# FX-Flash_DIP_rev_C.net
KiCad netlist of a schematic drawn in EAGLE
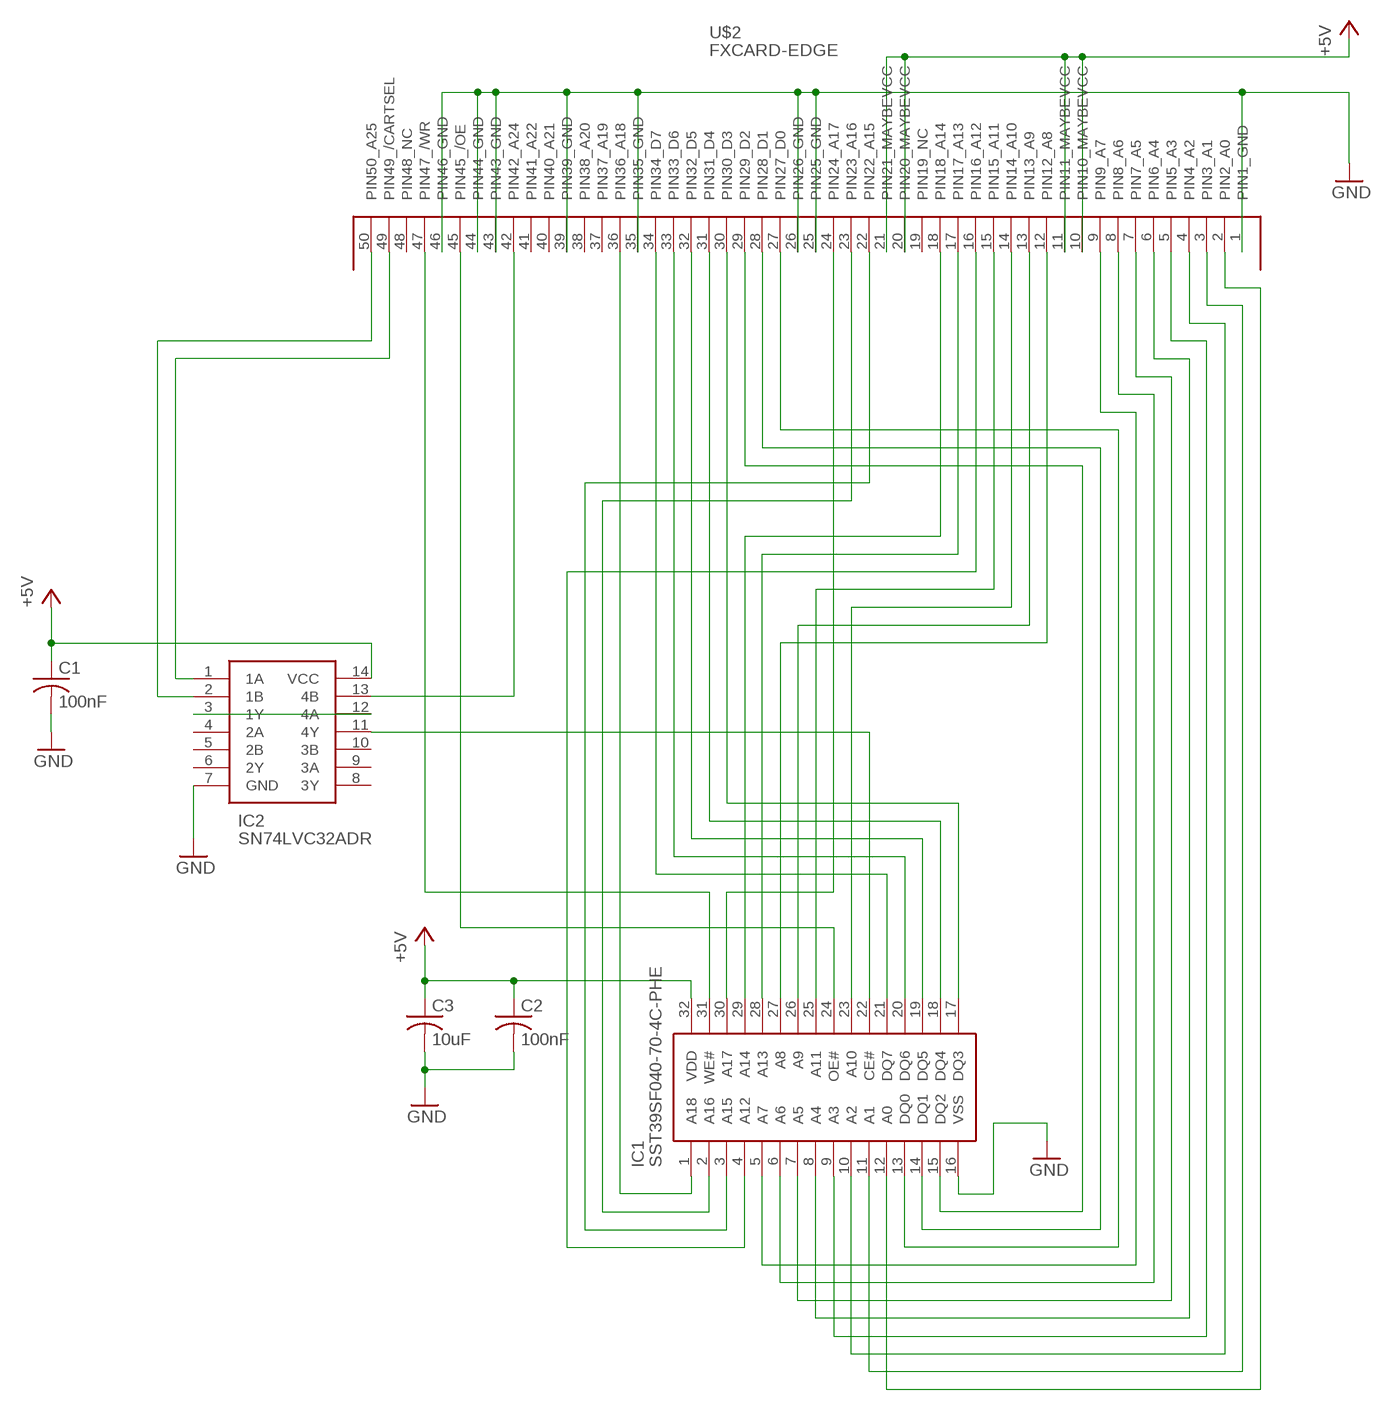
[diagram p0: schematic, sheet 1]

(export (version "E")
  (design (tool "Eeschema 10.0.6"))
  (components
    (comp (ref "C1")
      (value "100nF")
      (footprint "eagle-import:C0805")
      (libsource (lib "eagle-import") (part "C-USC0805"))
    )
    (comp (ref "C2")
      (value "100nF")
      (footprint "eagle-import:C0805")
      (libsource (lib "eagle-import") (part "C-USC0805"))
    )
    (comp (ref "C3")
      (value "10uF")
      (footprint "eagle-import:C0805")
      (libsource (lib "eagle-import") (part "C-USC0805"))
    )
    (comp (ref "IC1")
      (value "SST39SF040-70-4C-PHE")
      (footprint "eagle-import:DIP1556W56P254L4191H508Q32N")
      (fields
        (field (name "MOUSER_PART_NUMBER") "804-39SF0407CPHE")
        (field (name "RS_PART_NUMBER") "8104037P")
      )
      (libsource (lib "eagle-import") (part "SST39SF040-70-4C-PHE"))
    )
    (comp (ref "IC2")
      (value "SN74LVC32ADR")
      (footprint "eagle-import:SOIC127P600X175-14N")
      (fields (field (name "MOUSER_PART_NUMBER") "595-SN74LVC32ADR"))
      (libsource (lib "eagle-import") (part "SN74LVC32ADR"))
    )
    (comp (ref "U$2")
      (value "FXCARD-EDGE")
      (footprint "eagle-import:FXCARD-EDGE")
      (libsource (lib "eagle-import") (part "FXCARD-EDGE"))
    )
  )
  (nets
    (net (code "1") (name "+5V") (class "Default")
      (node (ref "C1") (pin "1") (pinfunction "1_1") (pintype "passive"))
      (node (ref "C2") (pin "1") (pinfunction "1_1") (pintype "passive"))
      (node (ref "C3") (pin "1") (pinfunction "1_1") (pintype "passive"))
      (node (ref "IC1") (pin "32") (pinfunction "VDD_32") (pintype "bidirectional"))
      (node (ref "IC2") (pin "14") (pinfunction "VCC_14") (pintype "bidirectional"))
      (node (ref "U$2") (pin "10") (pinfunction "PIN10_MAYBEVCC_10") (pintype "bidirectional"))
      (node (ref "U$2") (pin "11") (pinfunction "PIN11_MAYBEVCC_11") (pintype "bidirectional"))
      (node (ref "U$2") (pin "20") (pinfunction "PIN20_MAYBEVCC_20") (pintype "bidirectional"))
      (node (ref "U$2") (pin "21") (pinfunction "PIN21_MAYBEVCC_21") (pintype "bidirectional"))
    )
    (net (code "2") (name "GND") (class "Default")
      (node (ref "C1") (pin "2") (pinfunction "2_2") (pintype "passive"))
      (node (ref "C2") (pin "2") (pinfunction "2_2") (pintype "passive"))
      (node (ref "C3") (pin "2") (pinfunction "2_2") (pintype "passive"))
      (node (ref "IC1") (pin "16") (pinfunction "VSS_16") (pintype "bidirectional"))
      (node (ref "IC2") (pin "7") (pinfunction "GND_7") (pintype "bidirectional"))
      (node (ref "U$2") (pin "1") (pinfunction "PIN1_GND_1") (pintype "power_in"))
      (node (ref "U$2") (pin "25") (pinfunction "PIN25_GND_25") (pintype "power_in"))
      (node (ref "U$2") (pin "26") (pinfunction "PIN26_GND_26") (pintype "power_in"))
      (node (ref "U$2") (pin "35") (pinfunction "PIN35_GND_35") (pintype "power_in"))
      (node (ref "U$2") (pin "39") (pinfunction "PIN39_GND_39") (pintype "power_in"))
      (node (ref "U$2") (pin "43") (pinfunction "PIN43_GND_43") (pintype "power_in"))
      (node (ref "U$2") (pin "44") (pinfunction "PIN44_GND_44") (pintype "power_in"))
      (node (ref "U$2") (pin "46") (pinfunction "PIN46_GND_46") (pintype "power_in"))
    )
    (net (code "3") (name "Net-(IC1-A0)") (class "Default")
      (node (ref "IC1") (pin "12") (pinfunction "A0_12") (pintype "bidirectional"))
      (node (ref "U$2") (pin "2") (pinfunction "PIN2_A0_2") (pintype "bidirectional"))
    )
    (net (code "4") (name "Net-(IC1-A1)") (class "Default")
      (node (ref "IC1") (pin "11") (pinfunction "A1_11") (pintype "bidirectional"))
      (node (ref "U$2") (pin "3") (pinfunction "PIN3_A1_3") (pintype "bidirectional"))
    )
    (net (code "5") (name "Net-(IC1-A2)") (class "Default")
      (node (ref "IC1") (pin "10") (pinfunction "A2_10") (pintype "bidirectional"))
      (node (ref "U$2") (pin "4") (pinfunction "PIN4_A2_4") (pintype "bidirectional"))
    )
    (net (code "6") (name "Net-(IC1-A3)") (class "Default")
      (node (ref "IC1") (pin "9") (pinfunction "A3_9") (pintype "bidirectional"))
      (node (ref "U$2") (pin "5") (pinfunction "PIN5_A3_5") (pintype "bidirectional"))
    )
    (net (code "7") (name "Net-(IC1-A4)") (class "Default")
      (node (ref "IC1") (pin "8") (pinfunction "A4_8") (pintype "bidirectional"))
      (node (ref "U$2") (pin "6") (pinfunction "PIN6_A4_6") (pintype "bidirectional"))
    )
    (net (code "8") (name "Net-(IC1-A5)") (class "Default")
      (node (ref "IC1") (pin "7") (pinfunction "A5_7") (pintype "bidirectional"))
      (node (ref "U$2") (pin "7") (pinfunction "PIN7_A5_7") (pintype "bidirectional"))
    )
    (net (code "9") (name "Net-(IC1-A6)") (class "Default")
      (node (ref "IC1") (pin "6") (pinfunction "A6_6") (pintype "bidirectional"))
      (node (ref "U$2") (pin "8") (pinfunction "PIN8_A6_8") (pintype "bidirectional"))
    )
    (net (code "10") (name "Net-(IC1-A7)") (class "Default")
      (node (ref "IC1") (pin "5") (pinfunction "A7_5") (pintype "bidirectional"))
      (node (ref "U$2") (pin "9") (pinfunction "PIN9_A7_9") (pintype "bidirectional"))
    )
    (net (code "11") (name "Net-(IC1-A8)") (class "Default")
      (node (ref "IC1") (pin "27") (pinfunction "A8_27") (pintype "bidirectional"))
      (node (ref "U$2") (pin "12") (pinfunction "PIN12_A8_12") (pintype "bidirectional"))
    )
    (net (code "12") (name "Net-(IC1-A9)") (class "Default")
      (node (ref "IC1") (pin "26") (pinfunction "A9_26") (pintype "bidirectional"))
      (node (ref "U$2") (pin "13") (pinfunction "PIN13_A9_13") (pintype "bidirectional"))
    )
    (net (code "13") (name "Net-(IC1-A10)") (class "Default")
      (node (ref "IC1") (pin "23") (pinfunction "A10_23") (pintype "bidirectional"))
      (node (ref "U$2") (pin "14") (pinfunction "PIN14_A10_14") (pintype "bidirectional"))
    )
    (net (code "14") (name "Net-(IC1-A11)") (class "Default")
      (node (ref "IC1") (pin "25") (pinfunction "A11_25") (pintype "bidirectional"))
      (node (ref "U$2") (pin "15") (pinfunction "PIN15_A11_15") (pintype "bidirectional"))
    )
    (net (code "15") (name "Net-(IC1-A12)") (class "Default")
      (node (ref "IC1") (pin "4") (pinfunction "A12_4") (pintype "bidirectional"))
      (node (ref "U$2") (pin "16") (pinfunction "PIN16_A12_16") (pintype "bidirectional"))
    )
    (net (code "16") (name "Net-(IC1-A13)") (class "Default")
      (node (ref "IC1") (pin "28") (pinfunction "A13_28") (pintype "bidirectional"))
      (node (ref "U$2") (pin "17") (pinfunction "PIN17_A13_17") (pintype "bidirectional"))
    )
    (net (code "17") (name "Net-(IC1-A14)") (class "Default")
      (node (ref "IC1") (pin "29") (pinfunction "A14_29") (pintype "bidirectional"))
      (node (ref "U$2") (pin "18") (pinfunction "PIN18_A14_18") (pintype "bidirectional"))
    )
    (net (code "18") (name "Net-(IC1-A15)") (class "Default")
      (node (ref "IC1") (pin "3") (pinfunction "A15_3") (pintype "bidirectional"))
      (node (ref "U$2") (pin "22") (pinfunction "PIN22_A15_22") (pintype "bidirectional"))
    )
    (net (code "19") (name "Net-(IC1-A16)") (class "Default")
      (node (ref "IC1") (pin "2") (pinfunction "A16_2") (pintype "bidirectional"))
      (node (ref "U$2") (pin "23") (pinfunction "PIN23_A16_23") (pintype "bidirectional"))
    )
    (net (code "20") (name "Net-(IC1-A17)") (class "Default")
      (node (ref "IC1") (pin "30") (pinfunction "A17_30") (pintype "bidirectional"))
      (node (ref "U$2") (pin "24") (pinfunction "PIN24_A17_24") (pintype "bidirectional"))
    )
    (net (code "21") (name "Net-(IC1-A18)") (class "Default")
      (node (ref "IC1") (pin "1") (pinfunction "A18_1") (pintype "bidirectional"))
      (node (ref "U$2") (pin "36") (pinfunction "PIN36_A18_36") (pintype "bidirectional"))
    )
    (net (code "22") (name "Net-(IC1-CE#)") (class "Default")
      (node (ref "IC1") (pin "22") (pinfunction "CE#_22") (pintype "bidirectional"))
      (node (ref "IC2") (pin "11") (pinfunction "4Y_11") (pintype "bidirectional"))
    )
    (net (code "23") (name "Net-(IC1-DQ0)") (class "Default")
      (node (ref "IC1") (pin "13") (pinfunction "DQ0_13") (pintype "bidirectional"))
      (node (ref "U$2") (pin "27") (pinfunction "PIN27_D0_27") (pintype "bidirectional"))
    )
    (net (code "24") (name "Net-(IC1-DQ1)") (class "Default")
      (node (ref "IC1") (pin "14") (pinfunction "DQ1_14") (pintype "bidirectional"))
      (node (ref "U$2") (pin "28") (pinfunction "PIN28_D1_28") (pintype "bidirectional"))
    )
    (net (code "25") (name "Net-(IC1-DQ2)") (class "Default")
      (node (ref "IC1") (pin "15") (pinfunction "DQ2_15") (pintype "bidirectional"))
      (node (ref "U$2") (pin "29") (pinfunction "PIN29_D2_29") (pintype "bidirectional"))
    )
    (net (code "26") (name "Net-(IC1-DQ3)") (class "Default")
      (node (ref "IC1") (pin "17") (pinfunction "DQ3_17") (pintype "bidirectional"))
      (node (ref "U$2") (pin "30") (pinfunction "PIN30_D3_30") (pintype "bidirectional"))
    )
    (net (code "27") (name "Net-(IC1-DQ4)") (class "Default")
      (node (ref "IC1") (pin "18") (pinfunction "DQ4_18") (pintype "bidirectional"))
      (node (ref "U$2") (pin "31") (pinfunction "PIN31_D4_31") (pintype "bidirectional"))
    )
    (net (code "28") (name "Net-(IC1-DQ5)") (class "Default")
      (node (ref "IC1") (pin "19") (pinfunction "DQ5_19") (pintype "bidirectional"))
      (node (ref "U$2") (pin "32") (pinfunction "PIN32_D5_32") (pintype "bidirectional"))
    )
    (net (code "29") (name "Net-(IC1-DQ6)") (class "Default")
      (node (ref "IC1") (pin "20") (pinfunction "DQ6_20") (pintype "bidirectional"))
      (node (ref "U$2") (pin "33") (pinfunction "PIN33_D6_33") (pintype "bidirectional"))
    )
    (net (code "30") (name "Net-(IC1-DQ7)") (class "Default")
      (node (ref "IC1") (pin "21") (pinfunction "DQ7_21") (pintype "bidirectional"))
      (node (ref "U$2") (pin "34") (pinfunction "PIN34_D7_34") (pintype "bidirectional"))
    )
    (net (code "31") (name "Net-(IC1-OE#)") (class "Default")
      (node (ref "IC1") (pin "24") (pinfunction "OE#_24") (pintype "bidirectional"))
      (node (ref "U$2") (pin "45") (pinfunction "PIN45_/OE_45") (pintype "bidirectional"))
    )
    (net (code "32") (name "Net-(IC1-WE#)") (class "Default")
      (node (ref "IC1") (pin "31") (pinfunction "WE#_31") (pintype "bidirectional"))
      (node (ref "U$2") (pin "47") (pinfunction "PIN47_/WR_47") (pintype "bidirectional"))
    )
    (net (code "33") (name "Net-(IC2-1A)") (class "Default")
      (node (ref "IC2") (pin "1") (pinfunction "1A_1") (pintype "bidirectional"))
      (node (ref "U$2") (pin "49") (pinfunction "PIN49_/CARTSEL_49") (pintype "bidirectional"))
    )
    (net (code "34") (name "Net-(IC2-1B)") (class "Default")
      (node (ref "IC2") (pin "2") (pinfunction "1B_2") (pintype "bidirectional"))
      (node (ref "U$2") (pin "50") (pinfunction "PIN50_A25_50") (pintype "bidirectional"))
    )
    (net (code "35") (name "Net-(IC2-1Y)") (class "Default")
      (node (ref "IC2") (pin "12") (pinfunction "4A_12") (pintype "bidirectional"))
      (node (ref "IC2") (pin "3") (pinfunction "1Y_3") (pintype "bidirectional"))
    )
    (net (code "36") (name "Net-(IC2-4B)") (class "Default")
      (node (ref "IC2") (pin "13") (pinfunction "4B_13") (pintype "bidirectional"))
      (node (ref "U$2") (pin "42") (pinfunction "PIN42_A24_42") (pintype "bidirectional"))
    )
    (net (code "37") (name "unconnected-(IC2-2A-Pad4)") (class "Default")
      (node (ref "IC2") (pin "4") (pinfunction "2A_4") (pintype "bidirectional"))
    )
    (net (code "38") (name "unconnected-(IC2-2B-Pad5)") (class "Default")
      (node (ref "IC2") (pin "5") (pinfunction "2B_5") (pintype "bidirectional"))
    )
    (net (code "39") (name "unconnected-(IC2-2Y-Pad6)") (class "Default")
      (node (ref "IC2") (pin "6") (pinfunction "2Y_6") (pintype "bidirectional"))
    )
    (net (code "40") (name "unconnected-(IC2-3A-Pad9)") (class "Default")
      (node (ref "IC2") (pin "9") (pinfunction "3A_9") (pintype "bidirectional"))
    )
    (net (code "41") (name "unconnected-(IC2-3B-Pad10)") (class "Default")
      (node (ref "IC2") (pin "10") (pinfunction "3B_10") (pintype "bidirectional"))
    )
    (net (code "42") (name "unconnected-(IC2-3Y-Pad8)") (class "Default")
      (node (ref "IC2") (pin "8") (pinfunction "3Y_8") (pintype "bidirectional"))
    )
    (net (code "43") (name "unconnected-(U$2-PIN19_NC-Pad19)") (class "Default")
      (node (ref "U$2") (pin "19") (pinfunction "PIN19_NC_19") (pintype "bidirectional"))
    )
    (net (code "44") (name "unconnected-(U$2-PIN37_A19-Pad37)") (class "Default")
      (node (ref "U$2") (pin "37") (pinfunction "PIN37_A19_37") (pintype "bidirectional"))
    )
    (net (code "45") (name "unconnected-(U$2-PIN38_A20-Pad38)") (class "Default")
      (node (ref "U$2") (pin "38") (pinfunction "PIN38_A20_38") (pintype "bidirectional"))
    )
    (net (code "46") (name "unconnected-(U$2-PIN40_A21-Pad40)") (class "Default")
      (node (ref "U$2") (pin "40") (pinfunction "PIN40_A21_40") (pintype "bidirectional"))
    )
    (net (code "47") (name "unconnected-(U$2-PIN41_A22-Pad41)") (class "Default")
      (node (ref "U$2") (pin "41") (pinfunction "PIN41_A22_41") (pintype "bidirectional"))
    )
    (net (code "48") (name "unconnected-(U$2-PIN48_NC-Pad48)") (class "Default")
      (node (ref "U$2") (pin "48") (pinfunction "PIN48_NC_48") (pintype "bidirectional"))
    )
  )
)
